# Analogicas_Corriente.net
KiCad netlist of a schematic drawn in Altium Designer
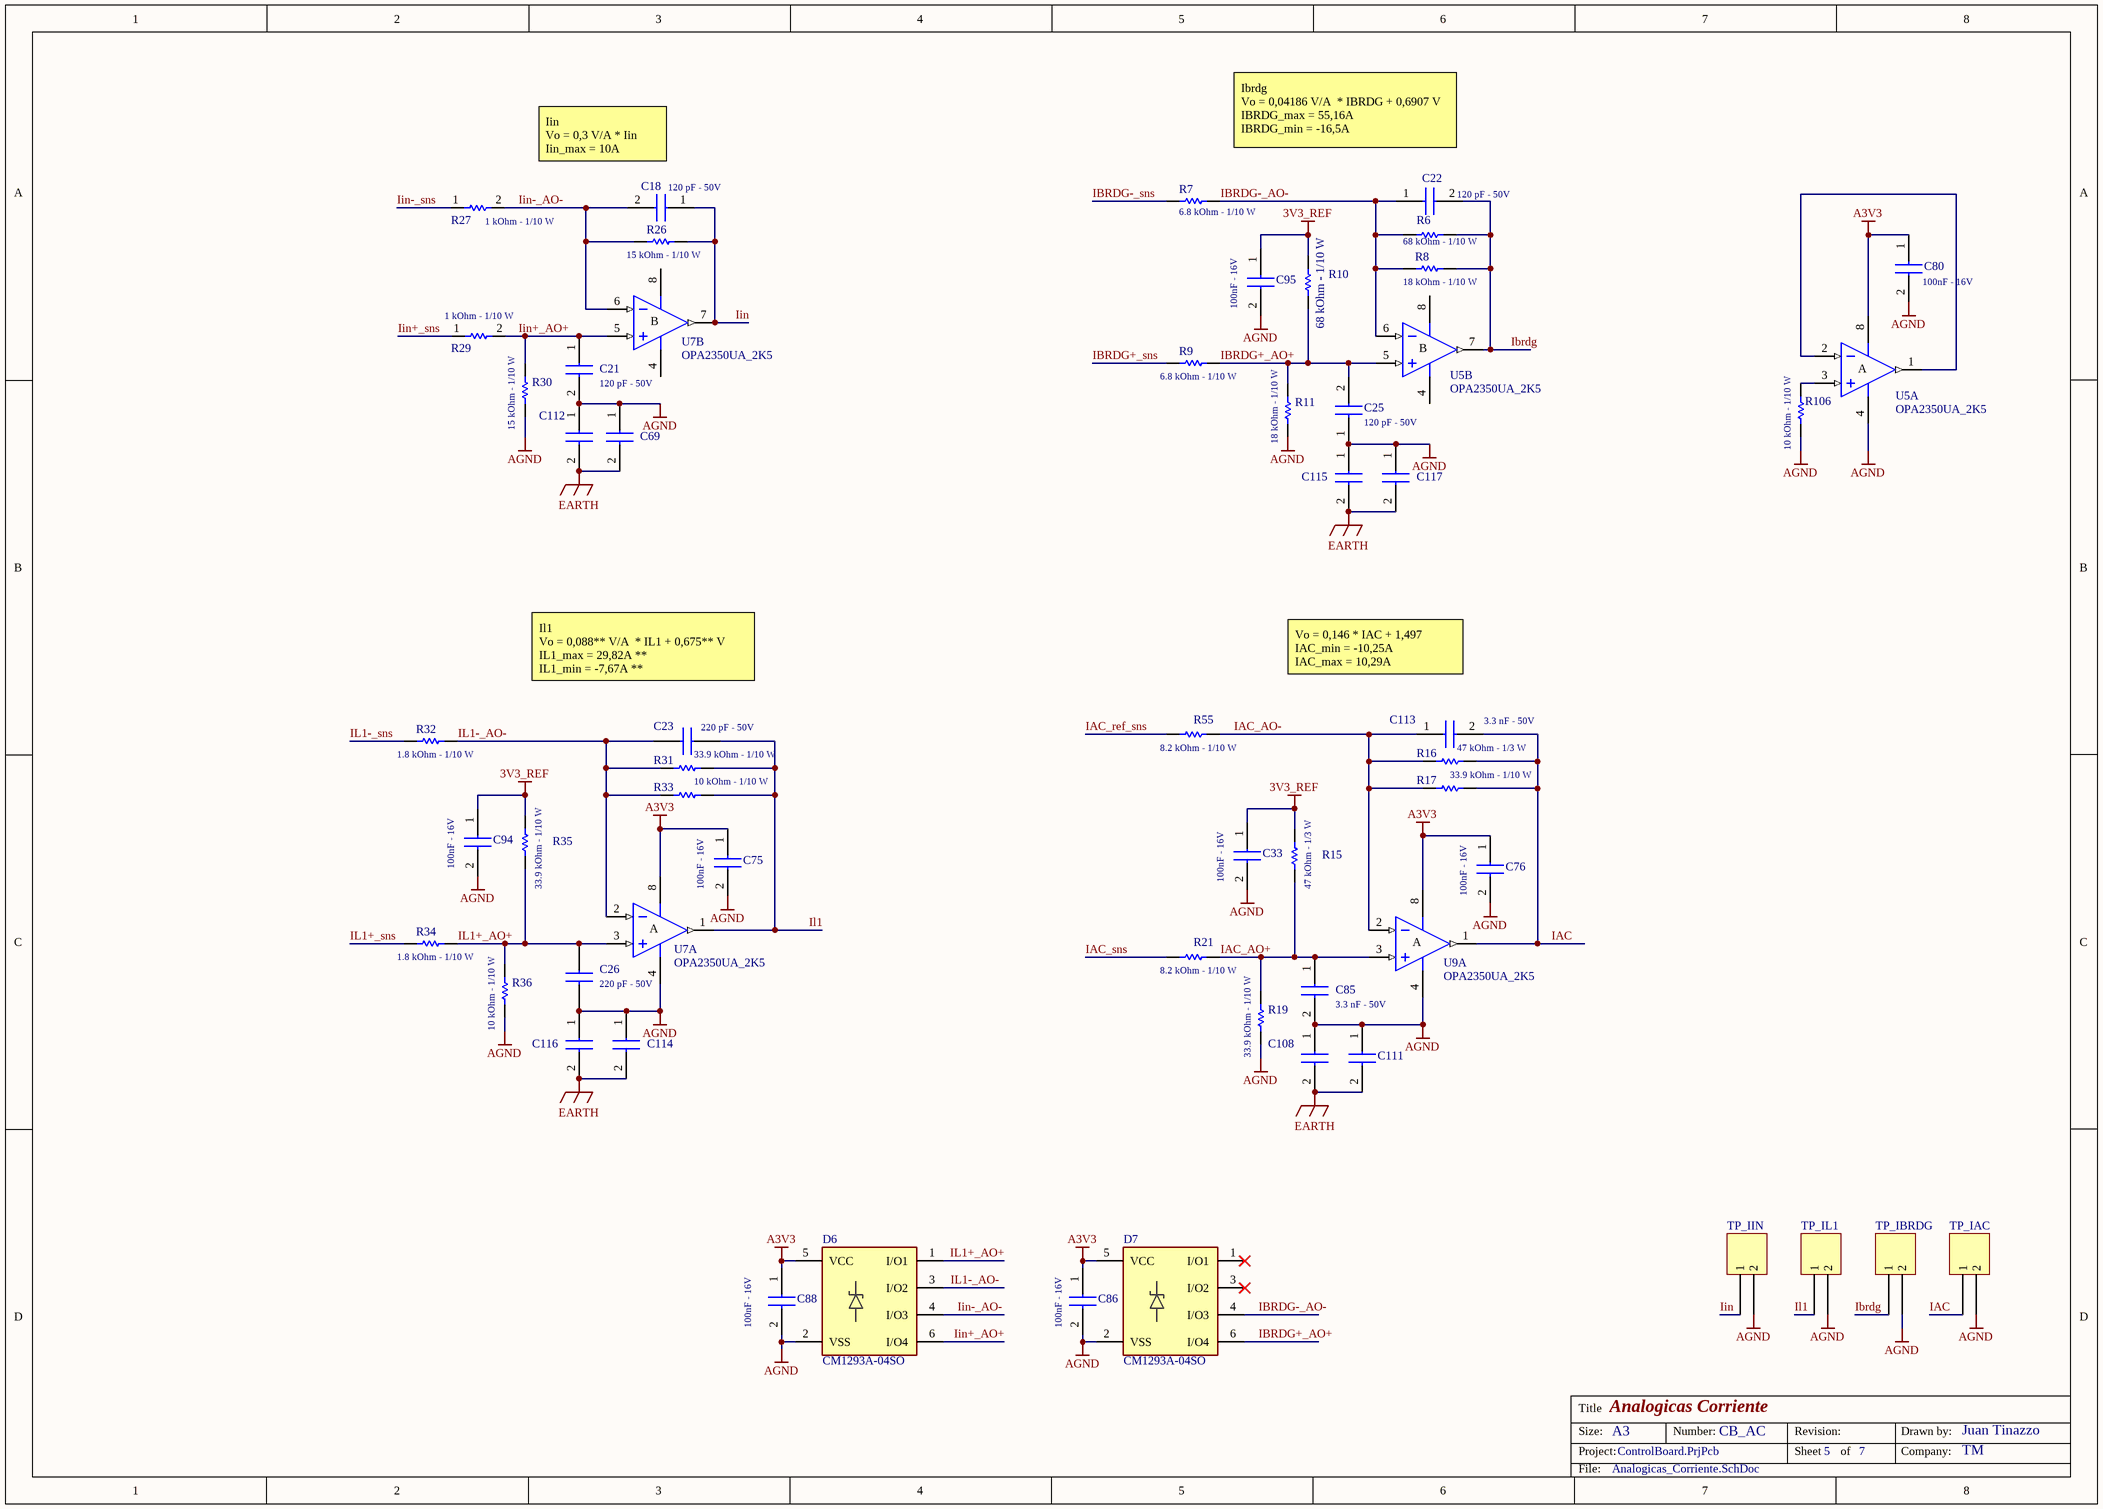
[diagram p0: Analogicas_Corriente.SchDoc]

(export (version "E")
  (design (tool "Eeschema 10.0.6"))
  (components
    (comp (ref "C18")
      (value "120 pF - 50V")
      (footprint "SamacSys:C0603")
      (description "Capacitor")
      (fields
        (field (name "MANUFACTURER_PART_NUMBER") "C0603C121J5GAC7411")
        (field (name "MOUSER PART NUMBER") "80-C0603C121J5GACLR")
      )
      (libsource (lib "SamacSys") (part "C0603C121J5GAC7411"))
    )
    (comp (ref "C21")
      (value "120 pF - 50V")
      (footprint "SamacSys:C0603")
      (description "Capacitor")
      (fields
        (field (name "MANUFACTURER_PART_NUMBER") "C0603C121J5GAC7411")
        (field (name "MOUSER PART NUMBER") "80-C0603C121J5GACLR")
      )
      (libsource (lib "SamacSys") (part "C0603C121J5GAC7411"))
    )
    (comp (ref "C22")
      (value "120 pF - 50V")
      (footprint "C0603")
      (description "Capacitor")
      (fields
        (field (name "MANUFACTURER_PART_NUMBER") "C0603C121J5GAC7411")
        (field (name "MOUSER PART NUMBER") "80-C0603C121J5GACLR")
      )
      (libsource (lib "SamacSys") (part "C0603C121J5GAC7411"))
    )
    (comp (ref "C23")
      (value "220 pF - 50V")
      (footprint "SamacSys:C0603")
      (description "Capacitor")
      (fields
        (field (name "MANUFACTURER_PART_NUMBER") "C0603C221J5HACAUTO")
        (field (name "MOUSER PART NUMBER") "80-C0603C221J5HAUTO")
      )
      (libsource (lib "SamacSys") (part "C0603C221J5HACAUTO"))
    )
    (comp (ref "C25")
      (value "120 pF - 50V")
      (footprint "C0603")
      (description "Capacitor")
      (fields
        (field (name "MANUFACTURER_PART_NUMBER") "C0603C121J5GAC7411")
        (field (name "MOUSER PART NUMBER") "80-C0603C121J5GACLR")
      )
      (libsource (lib "SamacSys") (part "C0603C121J5GAC7411"))
    )
    (comp (ref "C26")
      (value "220 pF - 50V")
      (footprint "SamacSys:C0603")
      (description "Capacitor")
      (fields
        (field (name "MANUFACTURER_PART_NUMBER") "C0603C221J5HACAUTO")
        (field (name "MOUSER PART NUMBER") "80-C0603C221J5HAUTO")
      )
      (libsource (lib "SamacSys") (part "C0603C221J5HACAUTO"))
    )
    (comp (ref "C33")
      (value "100nF - 16V")
      (footprint "CAPC1608X95N")
      (description "Capacitor")
      (fields
        (field (name "MANUFACTURER_PART_NUMBER") "EMK107B7104KA-T")
        (field (name "MOUSER PART NUMBER") "963-EMK107B7104KA-T")
      )
      (libsource (lib "SamacSys") (part "EMK107B7104KA-T"))
    )
    (comp (ref "C69")
      (value "C1206C102KGRACAUTO")
      (footprint "SamacSys:C1206")
      (description "Capacitor")
      (fields (field (name "MOUSER PART NUMBER") "80-C1206C102KGRAUTO"))
      (libsource (lib "SamacSys") (part "C1206C102KGRACAUTO"))
    )
    (comp (ref "C75")
      (value "100nF - 16V")
      (footprint "CAPC1608X95N")
      (description "Capacitor")
      (fields
        (field (name "MANUFACTURER_PART_NUMBER") "EMK107B7104KA-T")
        (field (name "MOUSER PART NUMBER") "963-EMK107B7104KA-T")
      )
      (libsource (lib "SamacSys") (part "EMK107B7104KA-T"))
    )
    (comp (ref "C76")
      (value "100nF - 16V")
      (footprint "CAPC1608X95N")
      (description "Capacitor")
      (fields
        (field (name "MANUFACTURER_PART_NUMBER") "EMK107B7104KA-T")
        (field (name "MOUSER PART NUMBER") "963-EMK107B7104KA-T")
      )
      (libsource (lib "SamacSys") (part "EMK107B7104KA-T"))
    )
    (comp (ref "C80")
      (value "100nF - 16V")
      (footprint "CAPC1608X95N")
      (description "Capacitor")
      (fields
        (field (name "MANUFACTURER_PART_NUMBER") "EMK107B7104KA-T")
        (field (name "MOUSER PART NUMBER") "963-EMK107B7104KA-T")
      )
      (libsource (lib "SamacSys") (part "EMK107B7104KA-T"))
    )
    (comp (ref "C85")
      (value "3.3 nF - 50V")
      (footprint "SamacSys:C0603")
      (description "Capacitor")
      (fields
        (field (name "MANUFACTURER_PART_NUMBER") "C0603C121J5GAC7411")
        (field (name "MOUSER PART NUMBER") "80-C0603C121J5GACLR")
      )
      (libsource (lib "SamacSys") (part "C0603C121J5GAC7411"))
    )
    (comp (ref "C86")
      (value "100nF - 16V")
      (footprint "CAPC1608X95N")
      (description "Capacitor")
      (fields
        (field (name "MANUFACTURER_PART_NUMBER") "EMK107B7104KA-T")
        (field (name "MOUSER PART NUMBER") "963-EMK107B7104KA-T")
      )
      (libsource (lib "SamacSys") (part "EMK107B7104KA-T"))
    )
    (comp (ref "C88")
      (value "100nF - 16V")
      (footprint "CAPC1608X95N")
      (description "Capacitor")
      (fields
        (field (name "MANUFACTURER_PART_NUMBER") "EMK107B7104KA-T")
        (field (name "MOUSER PART NUMBER") "963-EMK107B7104KA-T")
      )
      (libsource (lib "SamacSys") (part "EMK107B7104KA-T"))
    )
    (comp (ref "C94")
      (value "100nF - 16V")
      (footprint "CAPC1608X95N")
      (description "Capacitor")
      (fields
        (field (name "MANUFACTURER_PART_NUMBER") "EMK107B7104KA-T")
        (field (name "MOUSER PART NUMBER") "963-EMK107B7104KA-T")
      )
      (libsource (lib "SamacSys") (part "EMK107B7104KA-T"))
    )
    (comp (ref "C95")
      (value "100nF - 16V")
      (footprint "CAPC1608X95N")
      (description "Capacitor")
      (fields
        (field (name "MANUFACTURER_PART_NUMBER") "EMK107B7104KA-T")
        (field (name "MOUSER PART NUMBER") "963-EMK107B7104KA-T")
      )
      (libsource (lib "SamacSys") (part "EMK107B7104KA-T"))
    )
    (comp (ref "C108")
      (value "LDEQD1100KA5N00")
      (footprint "C_2220_1206")
      (description "Capacitor")
      (fields (field (name "MOUSER PART NUMBER") "80-LDEQD1100KA5N00"))
      (libsource (lib "*") (part "LDEQD1100KA5N00"))
    )
    (comp (ref "C111")
      (value "LDEQD1100KA5N00")
      (footprint "C_2220_1206")
      (description "Capacitor")
      (fields (field (name "MOUSER PART NUMBER") "80-LDEQD1100KA5N00"))
      (libsource (lib "*") (part "LDEQD1100KA5N00"))
    )
    (comp (ref "C112")
      (value "C1206C102KGRACAUTO")
      (footprint "SamacSys:C1206")
      (description "Capacitor")
      (fields (field (name "MOUSER PART NUMBER") "80-C1206C102KGRAUTO"))
      (libsource (lib "SamacSys") (part "C1206C102KGRACAUTO"))
    )
    (comp (ref "C113")
      (value "3.3 nF - 50V")
      (footprint "SamacSys:C0603")
      (description "Capacitor")
      (fields
        (field (name "MANUFACTURER_PART_NUMBER") "C0603C121J5GAC7411")
        (field (name "MOUSER PART NUMBER") "80-C0603C121J5GACLR")
      )
      (libsource (lib "SamacSys") (part "C0603C121J5GAC7411"))
    )
    (comp (ref "C114")
      (value "C1206C102KGRACAUTO")
      (footprint "SamacSys:C1206")
      (description "Capacitor")
      (fields (field (name "MOUSER PART NUMBER") "80-C1206C102KGRAUTO"))
      (libsource (lib "SamacSys") (part "C1206C102KGRACAUTO"))
    )
    (comp (ref "C115")
      (value "C1206C102KGRACAUTO")
      (footprint "SamacSys:C1206")
      (description "Capacitor")
      (fields (field (name "MOUSER PART NUMBER") "80-C1206C102KGRAUTO"))
      (libsource (lib "SamacSys") (part "C1206C102KGRACAUTO"))
    )
    (comp (ref "C116")
      (value "C1206C102KGRACAUTO")
      (footprint "SamacSys:C1206")
      (description "Capacitor")
      (fields (field (name "MOUSER PART NUMBER") "80-C1206C102KGRAUTO"))
      (libsource (lib "SamacSys") (part "C1206C102KGRACAUTO"))
    )
    (comp (ref "C117")
      (value "C1206C102KGRACAUTO")
      (footprint "SamacSys:C1206")
      (description "Capacitor")
      (fields (field (name "MOUSER PART NUMBER") "80-C1206C102KGRAUTO"))
      (libsource (lib "SamacSys") (part "C1206C102KGRACAUTO"))
    )
    (comp (ref "D6")
      (value "CM1293A-04SO")
      (footprint "SOT95P275X110-6N")
      (description "TVS Diode (Bi-directional)")
      (fields
        (field (name "MANUFACTURER_PART_NUMBER") "D5V0P4UR6SO-7")
        (field (name "MOUSER PART NUMBER") "748-CM1293A-04SO")
      )
      (libsource (lib "SamacSys") (part "CM1293A-04SO"))
    )
    (comp (ref "D7")
      (value "CM1293A-04SO")
      (footprint "SOT95P275X110-6N")
      (description "TVS Diode (Bi-directional)")
      (fields
        (field (name "MANUFACTURER_PART_NUMBER") "D5V0P4UR6SO-7")
        (field (name "MOUSER PART NUMBER") "748-CM1293A-04SO")
      )
      (libsource (lib "SamacSys") (part "CM1293A-04SO"))
    )
    (comp (ref "R6")
      (value "68 kOhm - 1/10 W")
      (footprint "SamacSys:RESC1608X55N")
      (description "Resistor")
      (fields
        (field (name "MANUFACTURER_PART_NUMBER") "ERJ-S03F6802V")
        (field (name "MOUSER PART NUMBER") "667-ERJ-S03F6802V")
      )
      (libsource (lib "SamacSys") (part "ERJ-S03F6802V"))
    )
    (comp (ref "R7")
      (value "6.8 kOhm - 1/10 W")
      (footprint "RESC1608X50N")
      (description "Resistor")
      (fields
        (field (name "MANUFACTURER_PART_NUMBER") "CRCW06036K80FKEA")
        (field (name "MOUSER PART NUMBER") "71-CRCW0603-6.8K-E3")
      )
      (libsource (lib "SamacSys") (part "CRCW06036K80FKEA"))
    )
    (comp (ref "R8")
      (value "18 kOhm - 1/10 W")
      (footprint "SamacSys:RESC1608X50N")
      (description "Resistor")
      (fields
        (field (name "MANUFACTURER_PART_NUMBER") "CRCW060318K0FKEA")
        (field (name "MOUSER PART NUMBER") "71-CRCW0603-18K-E3")
      )
      (libsource (lib "SamacSys") (part "CRCW060318K0FKEA"))
    )
    (comp (ref "R9")
      (value "6.8 kOhm - 1/10 W")
      (footprint "RESC1608X50N")
      (description "Resistor")
      (fields
        (field (name "MANUFACTURER_PART_NUMBER") "CRCW06036K80FKEA")
        (field (name "MOUSER PART NUMBER") "71-CRCW0603-6.8K-E3")
      )
      (libsource (lib "SamacSys") (part "CRCW06036K80FKEA"))
    )
    (comp (ref "R10")
      (value "68 kOhm - 1/10 W")
      (footprint "SamacSys:RESC1608X55N")
      (description "Resistor")
      (fields
        (field (name "MANUFACTURER_PART_NUMBER") "ERJ-S03F6802V")
        (field (name "MOUSER PART NUMBER") "667-ERJ-S03F6802V")
      )
      (libsource (lib "SamacSys") (part "ERJ-S03F6802V"))
    )
    (comp (ref "R11")
      (value "18 kOhm - 1/10 W")
      (footprint "SamacSys:RESC1608X50N")
      (description "Resistor")
      (fields
        (field (name "MANUFACTURER_PART_NUMBER") "CRCW060318K0FKEA")
        (field (name "MOUSER PART NUMBER") "71-CRCW0603-18K-E3")
      )
      (libsource (lib "SamacSys") (part "CRCW060318K0FKEA"))
    )
    (comp (ref "R15")
      (value "47 kOhm - 1/3 W")
      (footprint "SamacSys:RESC1608X50N")
      (description "Resistor")
      (fields
        (field (name "MANUFACTURER_PART_NUMBER") "CRCW060347K0FKEAHP")
        (field (name "MOUSER PART NUMBER") "71-CRCW060347K0FKEAH")
      )
      (libsource (lib "SamacSys") (part "CRCW060347K0FKEAHP"))
    )
    (comp (ref "R16")
      (value "47 kOhm - 1/3 W")
      (footprint "SamacSys:RESC1608X50N")
      (description "Resistor")
      (fields
        (field (name "MANUFACTURER_PART_NUMBER") "CRCW060347K0FKEAHP")
        (field (name "MOUSER PART NUMBER") "71-CRCW060347K0FKEAH")
      )
      (libsource (lib "SamacSys") (part "CRCW060347K0FKEAHP"))
    )
    (comp (ref "R17")
      (value "33.9 kOhm - 1/10 W")
      (footprint "SamacSys:RESC1608X50N")
      (description "Resistor")
      (fields
        (field (name "MANUFACTURER_PART_NUMBER") "CRCW060339K0FKEA")
        (field (name "MOUSER PART NUMBER") "71-CRCW0603-39K-E3")
      )
      (libsource (lib "SamacSys") (part "CRCW060339K0FKEA"))
    )
    (comp (ref "R19")
      (value "33.9 kOhm - 1/10 W")
      (footprint "SamacSys:RESC1608X50N")
      (description "Resistor")
      (fields
        (field (name "MANUFACTURER_PART_NUMBER") "CRCW060339K0FKEA")
        (field (name "MOUSER PART NUMBER") "71-CRCW0603-39K-E3")
      )
      (libsource (lib "SamacSys") (part "CRCW060339K0FKEA"))
    )
    (comp (ref "R21")
      (value "8.2 kOhm - 1/10 W")
      (footprint "SamacSys:RESC1608X55N")
      (description "Resistor")
      (fields
        (field (name "MANUFACTURER_PART_NUMBER") "CRG0603F8K2")
        (field (name "MOUSER PART NUMBER") "279-CRG0603F8K2")
      )
      (libsource (lib "SamacSys") (part "CRG0603F8K2"))
    )
    (comp (ref "R26")
      (value "15 kOhm - 1/10 W")
      (footprint "SamacSys:RESC1608X55N")
      (description "Resistor")
      (fields
        (field (name "MANUFACTURER_PART_NUMBER") "CRCW060315K0FKEAC")
        (field (name "MOUSER PART NUMBER") "71-CRCW060315K0FKEAC")
      )
      (libsource (lib "SamacSys") (part "CRCW060315K0FKEAC"))
    )
    (comp (ref "R27")
      (value "1 kOhm - 1/10 W")
      (footprint "RESC1608X55N")
      (description "Resistor")
      (fields
        (field (name "MANUFACTURER_PART_NUMBER") "CRCW06031K00FKEAC")
        (field (name "MOUSER PART NUMBER") "71-CRCW06031K00FKEAC")
      )
      (libsource (lib "SamacSys") (part "CRCW06031K00FKEAC"))
    )
    (comp (ref "R29")
      (value "1 kOhm - 1/10 W")
      (footprint "RESC1608X55N")
      (description "Resistor")
      (fields
        (field (name "MANUFACTURER_PART_NUMBER") "CRCW06031K00FKEAC")
        (field (name "MOUSER PART NUMBER") "71-CRCW06031K00FKEAC")
      )
      (libsource (lib "SamacSys") (part "CRCW06031K00FKEAC"))
    )
    (comp (ref "R30")
      (value "15 kOhm - 1/10 W")
      (footprint "SamacSys:RESC1608X55N")
      (description "Resistor")
      (fields
        (field (name "MANUFACTURER_PART_NUMBER") "CRCW060315K0FKEAC")
        (field (name "MOUSER PART NUMBER") "71-CRCW060315K0FKEAC")
      )
      (libsource (lib "SamacSys") (part "CRCW060315K0FKEAC"))
    )
    (comp (ref "R31")
      (value "33.9 kOhm - 1/10 W")
      (footprint "SamacSys:RESC1608X50N")
      (description "Resistor")
      (fields
        (field (name "MANUFACTURER_PART_NUMBER") "CRCW060339K0FKEA")
        (field (name "MOUSER PART NUMBER") "71-CRCW0603-39K-E3")
      )
      (libsource (lib "SamacSys") (part "CRCW060339K0FKEA"))
    )
    (comp (ref "R32")
      (value "1.8 kOhm - 1/10 W")
      (footprint "SamacSys:RESC1608X55N")
      (description "Resistor")
      (fields
        (field (name "MANUFACTURER_PART_NUMBER") "CRCW06031K80FKEAC")
        (field (name "MOUSER PART NUMBER") "71-CRCW06031K80FKEAC")
      )
      (libsource (lib "SamacSys") (part "CRCW06031K80FKEAC"))
    )
    (comp (ref "R33")
      (value "10 kOhm - 1/10 W")
      (footprint "SamacSys:RESC1608X50N")
      (description "Resistor")
      (fields
        (field (name "MANUFACTURER_PART_NUMBER") "CRCW060310K0FKEA")
        (field (name "MOUSER PART NUMBER") "71-CRCW0603-10K-E3")
      )
      (libsource (lib "SamacSys") (part "CRCW060310K0FKEA"))
    )
    (comp (ref "R34")
      (value "1.8 kOhm - 1/10 W")
      (footprint "SamacSys:RESC1608X55N")
      (description "Resistor")
      (fields
        (field (name "MANUFACTURER_PART_NUMBER") "CRCW06031K80FKEAC")
        (field (name "MOUSER PART NUMBER") "71-CRCW06031K80FKEAC")
      )
      (libsource (lib "SamacSys") (part "CRCW06031K80FKEAC"))
    )
    (comp (ref "R35")
      (value "33.9 kOhm - 1/10 W")
      (footprint "SamacSys:RESC1608X50N")
      (description "Resistor")
      (fields
        (field (name "MANUFACTURER_PART_NUMBER") "CRCW060339K0FKEA")
        (field (name "MOUSER PART NUMBER") "71-CRCW0603-39K-E3")
      )
      (libsource (lib "SamacSys") (part "CRCW060339K0FKEA"))
    )
    (comp (ref "R36")
      (value "10 kOhm - 1/10 W")
      (footprint "SamacSys:RESC1608X50N")
      (description "Resistor")
      (fields
        (field (name "MANUFACTURER_PART_NUMBER") "CRCW060310K0FKEA")
        (field (name "MOUSER PART NUMBER") "71-CRCW0603-10K-E3")
      )
      (libsource (lib "SamacSys") (part "CRCW060310K0FKEA"))
    )
    (comp (ref "R55")
      (value "8.2 kOhm - 1/10 W")
      (footprint "SamacSys:RESC1608X55N")
      (description "Resistor")
      (fields
        (field (name "MANUFACTURER_PART_NUMBER") "CRG0603F8K2")
        (field (name "MOUSER PART NUMBER") "279-CRG0603F8K2")
      )
      (libsource (lib "SamacSys") (part "CRG0603F8K2"))
    )
    (comp (ref "R106")
      (value "10 kOhm - 1/10 W")
      (footprint "RESC1608X50N")
      (description "Resistor")
      (fields
        (field (name "MANUFACTURER_PART_NUMBER") "CRCW060310K0FKEA")
        (field (name "MOUSER PART NUMBER") "71-CRCW0603-10K-E3")
      )
      (libsource (lib "SamacSys") (part "CRCW060310K0FKEA"))
    )
    (comp (ref "TP_IAC")
      (value "Test_Point")
      (footprint "Test Point")
      (description "Punta Prueba Osciloscopio")
      (fields (field (name "MANUFACTURER_PART_NUMBER") "PCB"))
      (libsource (lib "Componentes") (part "Test_Point"))
    )
    (comp (ref "TP_IBRDG")
      (value "Test_Point")
      (footprint "Test Point")
      (description "Punta Prueba Osciloscopio")
      (fields (field (name "MANUFACTURER_PART_NUMBER") "PCB"))
      (libsource (lib "Componentes") (part "Test_Point"))
    )
    (comp (ref "TP_IIN")
      (value "Test_Point")
      (footprint "Test Point")
      (description "Punta Prueba Osciloscopio")
      (fields (field (name "MANUFACTURER_PART_NUMBER") "PCB"))
      (libsource (lib "Componentes") (part "Test_Point"))
    )
    (comp (ref "TP_IL1")
      (value "Test_Point")
      (footprint "Test Point")
      (description "Punta Prueba Osciloscopio")
      (fields (field (name "MANUFACTURER_PART_NUMBER") "PCB"))
      (libsource (lib "Componentes") (part "Test_Point"))
    )
    (comp (ref "U5")
      (value "OPA2350UA_2K5")
      (footprint "SamacSys:SOIC127P600X175-8N")
      (description "Integrated Circuit")
      (fields
        (field (name "MANUFACTURER_PART_NUMBER") "OPA2350UA/2K5")
        (field (name "MOUSER PART NUMBER") "595-OPA2350UA/2K5")
      )
      (libsource (lib "SamacSys") (part "OPA2350UA_2K5"))
    )
    (comp (ref "U7")
      (value "OPA2350UA_2K5")
      (footprint "SamacSys:SOIC127P600X175-8N")
      (description "Integrated Circuit")
      (fields
        (field (name "MANUFACTURER_PART_NUMBER") "OPA2350UA/2K5")
        (field (name "MOUSER PART NUMBER") "595-OPA2350UA/2K5")
      )
      (libsource (lib "SamacSys") (part "OPA2350UA_2K5"))
    )
    (comp (ref "U9")
      (value "OPA2350UA_2K5")
      (footprint "SamacSys:SOIC127P600X175-8N")
      (description "Integrated Circuit")
      (fields
        (field (name "MANUFACTURER_PART_NUMBER") "OPA2350UA/2K5")
        (field (name "MOUSER PART NUMBER") "595-OPA2350UA/2K5")
      )
      (libsource (lib "SamacSys") (part "OPA2350UA_2K5"))
    )
  )
  (nets
    (net (code "1") (name "/IAC") (class "Default")
      (node (ref "C113") (pin "2") (pinfunction "2_2") (pintype "passive"))
      (node (ref "R16") (pin "1") (pinfunction "1_1") (pintype "passive"))
      (node (ref "R17") (pin "1") (pinfunction "1_1") (pintype "passive"))
      (node (ref "TP_IAC") (pin "1") (pinfunction "1_1") (pintype "passive"))
      (node (ref "U9") (pin "1") (pinfunction "OUT_1") (pintype "output"))
    )
    (net (code "2") (name "/IAC_AO+") (class "Default")
      (node (ref "C85") (pin "1") (pinfunction "1_1") (pintype "passive"))
      (node (ref "R15") (pin "1") (pinfunction "1_1") (pintype "passive"))
      (node (ref "R19") (pin "2") (pinfunction "2_2") (pintype "passive"))
      (node (ref "R21") (pin "2") (pinfunction "2_2") (pintype "passive"))
      (node (ref "U9") (pin "3") (pinfunction "IN+_3") (pintype "input"))
    )
    (net (code "3") (name "/IAC_AO-") (class "Default")
      (node (ref "C113") (pin "1") (pinfunction "1_1") (pintype "passive"))
      (node (ref "R16") (pin "2") (pinfunction "2_2") (pintype "passive"))
      (node (ref "R17") (pin "2") (pinfunction "2_2") (pintype "passive"))
      (node (ref "R55") (pin "2") (pinfunction "2_2") (pintype "passive"))
      (node (ref "U9") (pin "2") (pinfunction "IN-_2") (pintype "input"))
    )
    (net (code "4") (name "/IAC_ref_sns") (class "Default")
      (node (ref "R55") (pin "1") (pinfunction "1_1") (pintype "passive"))
    )
    (net (code "5") (name "/IAC_sns") (class "Default")
      (node (ref "R21") (pin "1") (pinfunction "1_1") (pintype "passive"))
    )
    (net (code "6") (name "/IBRDG+_AO+") (class "Default")
      (node (ref "C25") (pin "2") (pinfunction "2_2") (pintype "passive"))
      (node (ref "D7") (pin "6") (pinfunction "I/O4_6") (pintype "passive"))
      (node (ref "R10") (pin "1") (pinfunction "1_1") (pintype "passive"))
      (node (ref "R11") (pin "2") (pinfunction "2_2") (pintype "passive"))
      (node (ref "R9") (pin "1") (pinfunction "1_1") (pintype "passive"))
      (node (ref "U5") (pin "5") (pinfunction "IN+_5") (pintype "input"))
    )
    (net (code "7") (name "/IBRDG+_sns") (class "Default")
      (node (ref "R9") (pin "2") (pinfunction "2_2") (pintype "passive"))
    )
    (net (code "8") (name "/IBRDG-_AO-") (class "Default")
      (node (ref "C22") (pin "1") (pinfunction "1_1") (pintype "passive"))
      (node (ref "D7") (pin "4") (pinfunction "I/O3_4") (pintype "passive"))
      (node (ref "R6") (pin "2") (pinfunction "2_2") (pintype "passive"))
      (node (ref "R7") (pin "1") (pinfunction "1_1") (pintype "passive"))
      (node (ref "R8") (pin "2") (pinfunction "2_2") (pintype "passive"))
      (node (ref "U5") (pin "6") (pinfunction "IN-_6") (pintype "input"))
    )
    (net (code "9") (name "/IBRDG-_sns") (class "Default")
      (node (ref "R7") (pin "2") (pinfunction "2_2") (pintype "passive"))
    )
    (net (code "10") (name "/IL1+_AO+") (class "Default")
      (node (ref "C26") (pin "2") (pinfunction "2_2") (pintype "passive"))
      (node (ref "D6") (pin "1") (pinfunction "I/O1_1") (pintype "passive"))
      (node (ref "R34") (pin "1") (pinfunction "1_1") (pintype "passive"))
      (node (ref "R35") (pin "1") (pinfunction "1_1") (pintype "passive"))
      (node (ref "R36") (pin "1") (pinfunction "1_1") (pintype "passive"))
      (node (ref "U7") (pin "3") (pinfunction "IN+_3") (pintype "input"))
    )
    (net (code "11") (name "/IL1+_sns") (class "Default")
      (node (ref "R34") (pin "2") (pinfunction "2_2") (pintype "passive"))
    )
    (net (code "12") (name "/IL1-_AO-") (class "Default")
      (node (ref "C23") (pin "1") (pinfunction "1_1") (pintype "passive"))
      (node (ref "D6") (pin "3") (pinfunction "I/O2_3") (pintype "passive"))
      (node (ref "R31") (pin "2") (pinfunction "2_2") (pintype "passive"))
      (node (ref "R32") (pin "1") (pinfunction "1_1") (pintype "passive"))
      (node (ref "R33") (pin "2") (pinfunction "2_2") (pintype "passive"))
      (node (ref "U7") (pin "2") (pinfunction "IN-_2") (pintype "input"))
    )
    (net (code "13") (name "/IL1-_sns") (class "Default")
      (node (ref "R32") (pin "2") (pinfunction "2_2") (pintype "passive"))
    )
    (net (code "14") (name "/Ibrdg") (class "Default")
      (node (ref "C22") (pin "2") (pinfunction "2_2") (pintype "passive"))
      (node (ref "R6") (pin "1") (pinfunction "1_1") (pintype "passive"))
      (node (ref "R8") (pin "1") (pinfunction "1_1") (pintype "passive"))
      (node (ref "TP_IBRDG") (pin "1") (pinfunction "1_1") (pintype "passive"))
      (node (ref "U5") (pin "7") (pinfunction "OUT_7") (pintype "output"))
    )
    (net (code "15") (name "/Iin") (class "Default")
      (node (ref "C18") (pin "1") (pinfunction "1_1") (pintype "passive"))
      (node (ref "R26") (pin "1") (pinfunction "1_1") (pintype "passive"))
      (node (ref "TP_IIN") (pin "1") (pinfunction "1_1") (pintype "passive"))
      (node (ref "U7") (pin "7") (pinfunction "OUT_7") (pintype "output"))
    )
    (net (code "16") (name "/Iin+_AO+") (class "Default")
      (node (ref "C21") (pin "1") (pinfunction "1_1") (pintype "passive"))
      (node (ref "D6") (pin "6") (pinfunction "I/O4_6") (pintype "passive"))
      (node (ref "R29") (pin "2") (pinfunction "2_2") (pintype "passive"))
      (node (ref "R30") (pin "2") (pinfunction "2_2") (pintype "passive"))
      (node (ref "U7") (pin "5") (pinfunction "IN+_5") (pintype "input"))
    )
    (net (code "17") (name "/Iin+_sns") (class "Default")
      (node (ref "R29") (pin "1") (pinfunction "1_1") (pintype "passive"))
    )
    (net (code "18") (name "/Iin-_AO-") (class "Default")
      (node (ref "C18") (pin "2") (pinfunction "2_2") (pintype "passive"))
      (node (ref "D6") (pin "4") (pinfunction "I/O3_4") (pintype "passive"))
      (node (ref "R26") (pin "2") (pinfunction "2_2") (pintype "passive"))
      (node (ref "R27") (pin "2") (pinfunction "2_2") (pintype "passive"))
      (node (ref "U7") (pin "6") (pinfunction "IN-_6") (pintype "input"))
    )
    (net (code "19") (name "/Iin-_sns") (class "Default")
      (node (ref "R27") (pin "1") (pinfunction "1_1") (pintype "passive"))
    )
    (net (code "20") (name "/Il1") (class "Default")
      (node (ref "C23") (pin "2") (pinfunction "2_2") (pintype "passive"))
      (node (ref "R31") (pin "1") (pinfunction "1_1") (pintype "passive"))
      (node (ref "R33") (pin "1") (pinfunction "1_1") (pintype "passive"))
      (node (ref "TP_IL1") (pin "1") (pinfunction "1_1") (pintype "passive"))
      (node (ref "U7") (pin "1") (pinfunction "OUT_1") (pintype "output"))
    )
    (net (code "21") (name "3V3_REF") (class "Default")
      (node (ref "C33") (pin "1") (pinfunction "1_1") (pintype "passive"))
      (node (ref "C94") (pin "1") (pinfunction "1_1") (pintype "passive"))
      (node (ref "C95") (pin "1") (pinfunction "1_1") (pintype "passive"))
      (node (ref "R10") (pin "2") (pinfunction "2_2") (pintype "passive"))
      (node (ref "R15") (pin "2") (pinfunction "2_2") (pintype "passive"))
      (node (ref "R35") (pin "2") (pinfunction "2_2") (pintype "passive"))
    )
    (net (code "22") (name "A3V3") (class "Default")
      (node (ref "C75") (pin "1") (pinfunction "1_1") (pintype "passive"))
      (node (ref "C76") (pin "1") (pinfunction "1_1") (pintype "passive"))
      (node (ref "C80") (pin "1") (pinfunction "1_1") (pintype "passive"))
      (node (ref "C86") (pin "1") (pinfunction "1_1") (pintype "passive"))
      (node (ref "C88") (pin "1") (pinfunction "1_1") (pintype "passive"))
      (node (ref "D6") (pin "5") (pinfunction "VCC_5") (pintype "passive"))
      (node (ref "D7") (pin "5") (pinfunction "VCC_5") (pintype "passive"))
      (node (ref "U5") (pin "8") (pinfunction "V+_8") (pintype "power_in"))
      (node (ref "U7") (pin "8") (pinfunction "V+_8") (pintype "power_in"))
      (node (ref "U9") (pin "8") (pinfunction "V+_8") (pintype "power_in"))
    )
    (net (code "23") (name "AGND") (class "Default")
      (node (ref "C108") (pin "1") (pinfunction "1_1") (pintype "passive"))
      (node (ref "C111") (pin "1") (pinfunction "1_1") (pintype "passive"))
      (node (ref "C112") (pin "1") (pinfunction "1_1") (pintype "passive"))
      (node (ref "C114") (pin "1") (pinfunction "1_1") (pintype "passive"))
      (node (ref "C115") (pin "1") (pinfunction "1_1") (pintype "passive"))
      (node (ref "C116") (pin "1") (pinfunction "1_1") (pintype "passive"))
      (node (ref "C117") (pin "1") (pinfunction "1_1") (pintype "passive"))
      (node (ref "C21") (pin "2") (pinfunction "2_2") (pintype "passive"))
      (node (ref "C25") (pin "1") (pinfunction "1_1") (pintype "passive"))
      (node (ref "C26") (pin "1") (pinfunction "1_1") (pintype "passive"))
      (node (ref "C33") (pin "2") (pinfunction "2_2") (pintype "passive"))
      (node (ref "C69") (pin "1") (pinfunction "1_1") (pintype "passive"))
      (node (ref "C75") (pin "2") (pinfunction "2_2") (pintype "passive"))
      (node (ref "C76") (pin "2") (pinfunction "2_2") (pintype "passive"))
      (node (ref "C80") (pin "2") (pinfunction "2_2") (pintype "passive"))
      (node (ref "C85") (pin "2") (pinfunction "2_2") (pintype "passive"))
      (node (ref "C86") (pin "2") (pinfunction "2_2") (pintype "passive"))
      (node (ref "C88") (pin "2") (pinfunction "2_2") (pintype "passive"))
      (node (ref "C94") (pin "2") (pinfunction "2_2") (pintype "passive"))
      (node (ref "C95") (pin "2") (pinfunction "2_2") (pintype "passive"))
      (node (ref "D6") (pin "2") (pinfunction "VSS_2") (pintype "passive"))
      (node (ref "D7") (pin "2") (pinfunction "VSS_2") (pintype "passive"))
      (node (ref "R106") (pin "1") (pinfunction "1_1") (pintype "passive"))
      (node (ref "R11") (pin "1") (pinfunction "1_1") (pintype "passive"))
      (node (ref "R19") (pin "1") (pinfunction "1_1") (pintype "passive"))
      (node (ref "R30") (pin "1") (pinfunction "1_1") (pintype "passive"))
      (node (ref "R36") (pin "2") (pinfunction "2_2") (pintype "passive"))
      (node (ref "TP_IAC") (pin "2") (pinfunction "2_2") (pintype "passive"))
      (node (ref "TP_IBRDG") (pin "2") (pinfunction "2_2") (pintype "passive"))
      (node (ref "TP_IIN") (pin "2") (pinfunction "2_2") (pintype "passive"))
      (node (ref "TP_IL1") (pin "2") (pinfunction "2_2") (pintype "passive"))
      (node (ref "U5") (pin "4") (pinfunction "V-_4") (pintype "power_in"))
      (node (ref "U7") (pin "4") (pinfunction "V-_4") (pintype "power_in"))
      (node (ref "U9") (pin "4") (pinfunction "V-_4") (pintype "power_in"))
    )
    (net (code "24") (name "EARTH") (class "Default")
      (node (ref "C108") (pin "2") (pinfunction "2_2") (pintype "passive"))
      (node (ref "C111") (pin "2") (pinfunction "2_2") (pintype "passive"))
      (node (ref "C112") (pin "2") (pinfunction "2_2") (pintype "passive"))
      (node (ref "C114") (pin "2") (pinfunction "2_2") (pintype "passive"))
      (node (ref "C115") (pin "2") (pinfunction "2_2") (pintype "passive"))
      (node (ref "C116") (pin "2") (pinfunction "2_2") (pintype "passive"))
      (node (ref "C117") (pin "2") (pinfunction "2_2") (pintype "passive"))
      (node (ref "C69") (pin "2") (pinfunction "2_2") (pintype "passive"))
    )
    (net (code "25") (name "Net-(U5A-IN+)") (class "Default")
      (node (ref "R106") (pin "2") (pinfunction "2_2") (pintype "passive"))
      (node (ref "U5") (pin "3") (pinfunction "IN+_3") (pintype "input"))
    )
    (net (code "26") (name "Net-(U5A-IN-)") (class "Default")
      (node (ref "U5") (pin "1") (pinfunction "OUT_1") (pintype "output"))
      (node (ref "U5") (pin "2") (pinfunction "IN-_2") (pintype "input"))
    )
    (net (code "27") (name "unconnected-(D7-I{slash}O1-Pad1)") (class "Default")
      (node (ref "D7") (pin "1") (pinfunction "I/O1_1") (pintype "passive+no_connect"))
    )
    (net (code "28") (name "unconnected-(D7-I{slash}O2-Pad3)") (class "Default")
      (node (ref "D7") (pin "3") (pinfunction "I/O2_3") (pintype "passive+no_connect"))
    )
    (net (code "29") (name "unconnected-(U5B-V+-Pad8)") (class "Default")
      (node (ref "U5") (pin "8") (pinfunction "V+_8") (pintype "power_in"))
    )
    (net (code "30") (name "unconnected-(U5B-V--Pad4)") (class "Default")
      (node (ref "U5") (pin "4") (pinfunction "V-_4") (pintype "power_in"))
    )
    (net (code "31") (name "unconnected-(U7B-V+-Pad8)") (class "Default")
      (node (ref "U7") (pin "8") (pinfunction "V+_8") (pintype "power_in"))
    )
    (net (code "32") (name "unconnected-(U7B-V--Pad4)") (class "Default")
      (node (ref "U7") (pin "4") (pinfunction "V-_4") (pintype "power_in"))
    )
  )
)
